# Servo_controller.net
KiCad netlist of a schematic drawn in Altium Designer
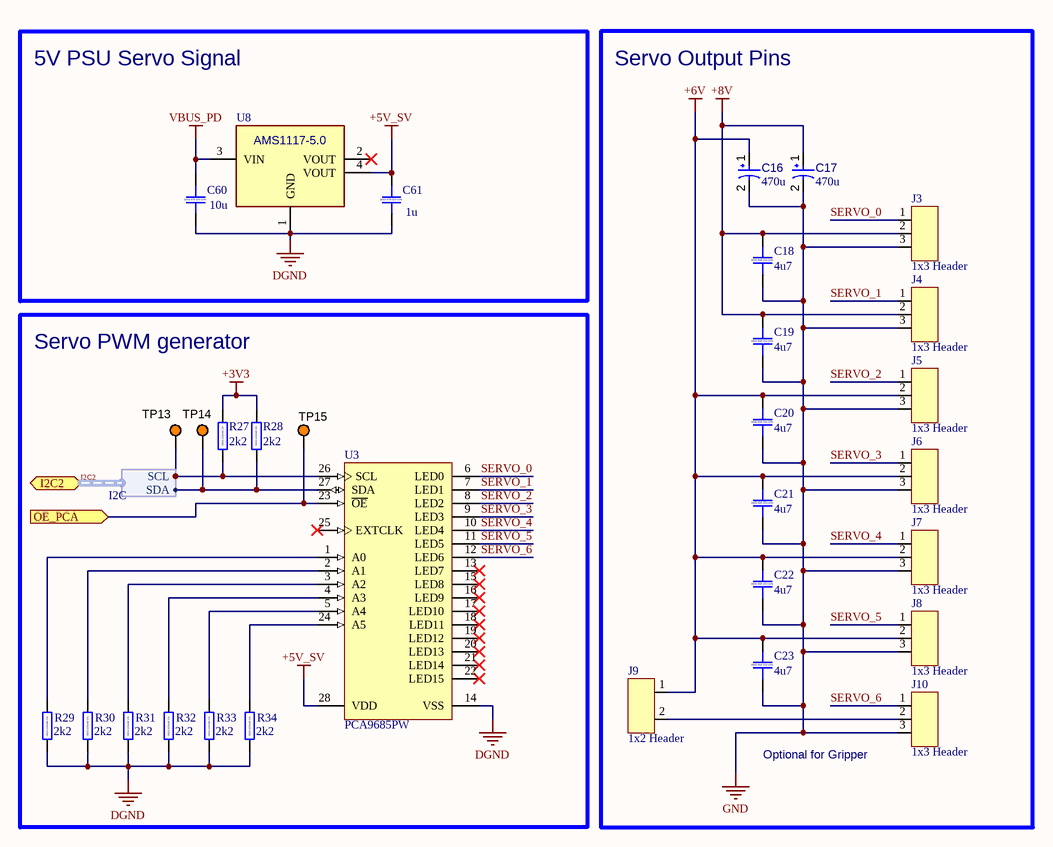
[diagram p0: Servo_controller.SchDoc]

(export (version "E")
  (design (tool "Eeschema 10.0.6"))
  (components
    (comp (ref "C16")
      (value "470u")
      (footprint "CAPPR65-500-2000X1000X2200")
      (description "Aluminum Electrolytic Capacitor, 2-Pin THD")
      (fields (field (name "MANUFACTURER") "Panasonic") (field (name "TOLERANCE") "20%"))
      (libsource (lib "Leonhard Waibl") (part "CAP-P-2"))
    )
    (comp (ref "C17")
      (value "470u")
      (footprint "CAPPR65-500-2000X1000X2200")
      (description "Aluminum Electrolytic Capacitor, 2-Pin THD")
      (fields (field (name "MANUFACTURER") "Panasonic") (field (name "TOLERANCE") "20%"))
      (libsource (lib "Leonhard Waibl") (part "CAP-P-2"))
    )
    (comp (ref "C18")
      (value "4u7")
      (footprint "CAP_0805")
      (description "Capacitor SMD 0805")
      (fields (field (name "SOURCE") "Schematic-Lib-PhilsLab.SchLib"))
      (libsource (lib "") (part "CAP_EL_NP_5MM_1"))
    )
    (comp (ref "C19")
      (value "4u7")
      (footprint "CAP_0805")
      (description "Capacitor SMD 0805")
      (fields (field (name "SOURCE") "Schematic-Lib-PhilsLab.SchLib"))
      (libsource (lib "") (part "CAP_EL_NP_5MM_1"))
    )
    (comp (ref "C20")
      (value "4u7")
      (footprint "CAP_0805")
      (description "Capacitor SMD 0805")
      (fields (field (name "SOURCE") "Schematic-Lib-PhilsLab.SchLib"))
      (libsource (lib "") (part "CAP_EL_NP_5MM_1"))
    )
    (comp (ref "C21")
      (value "4u7")
      (footprint "CAP_0805")
      (description "Capacitor SMD 0805")
      (fields (field (name "SOURCE") "Schematic-Lib-PhilsLab.SchLib"))
      (libsource (lib "") (part "CAP_EL_NP_5MM_1"))
    )
    (comp (ref "C22")
      (value "4u7")
      (footprint "CAP_0805")
      (description "Capacitor SMD 0805")
      (fields (field (name "SOURCE") "Schematic-Lib-PhilsLab.SchLib"))
      (libsource (lib "") (part "CAP_EL_NP_5MM_1"))
    )
    (comp (ref "C23")
      (value "4u7")
      (footprint "CAP_0805")
      (description "Capacitor SMD 0805")
      (fields (field (name "SOURCE") "Schematic-Lib-PhilsLab.SchLib"))
      (libsource (lib "") (part "CAP_EL_NP_5MM_1"))
    )
    (comp (ref "C60")
      (value "10u")
      (footprint "CAP_0603")
      (description "Capacitor SMD 0603")
      (fields (field (name "SOURCE") "Schematic-Lib-PhilsLab.SchLib"))
      (libsource (lib "Leonhard Waibl") (part "CAP_EL_NP_5MM"))
    )
    (comp (ref "C61")
      (value "1u")
      (footprint "CAP_0603")
      (description "Capacitor SMD 0603")
      (fields (field (name "SOURCE") "Schematic-Lib-PhilsLab.SchLib"))
      (libsource (lib "Leonhard Waibl") (part "CAP_EL_NP_5MM"))
    )
    (comp (ref "J3")
      (value "1x3 Header")
      (footprint "1x4 Header-Footprint-1")
      (libsource (lib "Leonhard Waibl") (part "1x3 Header"))
    )
    (comp (ref "J4")
      (value "1x3 Header")
      (footprint "1x4 Header-Footprint-1")
      (libsource (lib "Leonhard Waibl") (part "1x3 Header"))
    )
    (comp (ref "J5")
      (value "1x3 Header")
      (footprint "1x4 Header-Footprint-1")
      (libsource (lib "Leonhard Waibl") (part "1x3 Header"))
    )
    (comp (ref "J6")
      (value "1x3 Header")
      (footprint "1x4 Header-Footprint-1")
      (libsource (lib "Leonhard Waibl") (part "1x3 Header"))
    )
    (comp (ref "J7")
      (value "1x3 Header")
      (footprint "1x4 Header-Footprint-1")
      (libsource (lib "Leonhard Waibl") (part "1x3 Header"))
    )
    (comp (ref "J8")
      (value "1x3 Header")
      (footprint "1x4 Header-Footprint-1")
      (libsource (lib "Leonhard Waibl") (part "1x3 Header"))
    )
    (comp (ref "J9")
      (value "1x2 Header")
      (footprint "1x2 Header-Footprint-1")
      (libsource (lib "Leonhard Waibl") (part "1x2 Header-Symbol-1"))
    )
    (comp (ref "J10")
      (value "1x3 Header")
      (footprint "1x4 Header-Footprint-1")
      (libsource (lib "Leonhard Waibl") (part "1x3 Header"))
    )
    (comp (ref "R27")
      (value "2k2")
      (footprint "RES_0603")
      (description "Resistor 0603 100mW 1%")
      (fields (field (name "SOURCE") "Schematic-Lib-PhilsLab.SchLib"))
      (libsource (lib "Leonhard Waibl") (part "RES_5931"))
    )
    (comp (ref "R28")
      (value "2k2")
      (footprint "RES_0603")
      (description "Resistor 0603 100mW 1%")
      (fields (field (name "SOURCE") "Schematic-Lib-PhilsLab.SchLib"))
      (libsource (lib "Leonhard Waibl") (part "RES_5931"))
    )
    (comp (ref "R29")
      (value "2k2")
      (footprint "RES_0603")
      (description "Resistor 0603 100mW 1%")
      (fields (field (name "SOURCE") "Schematic-Lib-PhilsLab.SchLib"))
      (libsource (lib "Leonhard Waibl") (part "RES_5931"))
    )
    (comp (ref "R30")
      (value "2k2")
      (footprint "RES_0603")
      (description "Resistor 0603 100mW 1%")
      (fields (field (name "SOURCE") "Schematic-Lib-PhilsLab.SchLib"))
      (libsource (lib "Leonhard Waibl") (part "RES_5931"))
    )
    (comp (ref "R31")
      (value "2k2")
      (footprint "RES_0603")
      (description "Resistor 0603 100mW 1%")
      (fields (field (name "SOURCE") "Schematic-Lib-PhilsLab.SchLib"))
      (libsource (lib "Leonhard Waibl") (part "RES_5931"))
    )
    (comp (ref "R32")
      (value "2k2")
      (footprint "RES_0603")
      (description "Resistor 0603 100mW 1%")
      (fields (field (name "SOURCE") "Schematic-Lib-PhilsLab.SchLib"))
      (libsource (lib "Leonhard Waibl") (part "RES_5931"))
    )
    (comp (ref "R33")
      (value "2k2")
      (footprint "RES_0603")
      (description "Resistor 0603 100mW 1%")
      (fields (field (name "SOURCE") "Schematic-Lib-PhilsLab.SchLib"))
      (libsource (lib "Leonhard Waibl") (part "RES_5931"))
    )
    (comp (ref "R34")
      (value "2k2")
      (footprint "RES_0603")
      (description "Resistor 0603 100mW 1%")
      (fields (field (name "SOURCE") "Schematic-Lib-PhilsLab.SchLib"))
      (libsource (lib "Leonhard Waibl") (part "RES_5931"))
    )
    (comp (ref "TP13")
      (value "5003")
      (footprint "KSTN-5003")
      (description "Test Point, Orange, Height 4.6 mm, Tail Length 3 mm, 1-Pin THD, RoHS")
      (fields (field (name "MANUFACTURER") "Keystone"))
      (libsource (lib "Leonhard Waibl") (part "TESTPOINT_ORANGE"))
    )
    (comp (ref "TP14")
      (value "5003")
      (footprint "KSTN-5003")
      (description "Test Point, Orange, Height 4.6 mm, Tail Length 3 mm, 1-Pin THD, RoHS")
      (fields (field (name "MANUFACTURER") "Keystone"))
      (libsource (lib "Leonhard Waibl") (part "TESTPOINT_ORANGE"))
    )
    (comp (ref "TP15")
      (value "5003")
      (footprint "KSTN-5003")
      (description "Test Point, Orange, Height 4.6 mm, Tail Length 3 mm, 1-Pin THD, RoHS")
      (fields (field (name "MANUFACTURER") "Keystone"))
      (libsource (lib "Leonhard Waibl") (part "TESTPOINT_ORANGE"))
    )
    (comp (ref "U3")
      (value "PCA9685PW")
      (footprint "SOT361-1_V")
      (fields (field (name "PARTNUMBER") "PCA9685"))
      (libsource (lib "Altium Content Vault") (part "NXP-PCA9685-SOT361-1"))
    )
    (comp (ref "U8")
      (value "AMS1117-5.0")
      (footprint "FP-AMS1117-IPC_B")
      (description "Fixed Positive LDO Regulator, 5.0V, 1.3V Dropout, PDSO3")
      (libsource (lib "Leonhard Waibl") (part "8bdbb5f8e77002000e30dd2845d0354"))
    )
  )
  (nets
    (net (code "2") (name "+3V3") (class "Default")
      (node (ref "R27") (pin "2") (pinfunction "2_2") (pintype "passive"))
      (node (ref "R28") (pin "2") (pinfunction "2_2") (pintype "passive"))
    )
    (net (code "3") (name "+5V_SV") (class "Default")
      (node (ref "C61") (pin "1") (pinfunction "1_1") (pintype "passive"))
      (node (ref "U3") (pin "28") (pinfunction "VDD_28") (pintype "power_in"))
      (node (ref "U8") (pin "4") (pinfunction "VOUT_4") (pintype "passive"))
    )
    (net (code "4") (name "+6V") (class "Default")
      (node (ref "C16") (pin "1") (pinfunction "1_1") (pintype "passive"))
      (node (ref "C20") (pin "2") (pinfunction "2_2") (pintype "passive"))
      (node (ref "C21") (pin "2") (pinfunction "2_2") (pintype "passive"))
      (node (ref "C22") (pin "2") (pinfunction "2_2") (pintype "passive"))
      (node (ref "C23") (pin "2") (pinfunction "2_2") (pintype "passive"))
      (node (ref "J5") (pin "2") (pinfunction "2_2") (pintype "passive"))
      (node (ref "J6") (pin "2") (pinfunction "2_2") (pintype "passive"))
      (node (ref "J7") (pin "2") (pinfunction "2_2") (pintype "passive"))
      (node (ref "J8") (pin "2") (pinfunction "2_2") (pintype "passive"))
      (node (ref "J9") (pin "1") (pinfunction "1_1") (pintype "passive"))
    )
    (net (code "5") (name "+8V") (class "Default")
      (node (ref "C17") (pin "1") (pinfunction "1_1") (pintype "passive"))
      (node (ref "C18") (pin "2") (pinfunction "2_2") (pintype "passive"))
      (node (ref "C19") (pin "2") (pinfunction "2_2") (pintype "passive"))
      (node (ref "J3") (pin "2") (pinfunction "2_2") (pintype "passive"))
      (node (ref "J4") (pin "2") (pinfunction "2_2") (pintype "passive"))
    )
    (net (code "7") (name "/OE_PCA") (class "Default")
      (node (ref "TP15") (pin "1") (pinfunction "1_1") (pintype "passive"))
      (node (ref "U3") (pin "23") (pinfunction "~{OE}_23") (pintype "input"))
    )
    (net (code "8") (name "/SERVO_0") (class "Default")
      (node (ref "J3") (pin "1") (pinfunction "1_1") (pintype "passive"))
      (node (ref "U3") (pin "6") (pinfunction "LED0_6") (pintype "tri_state"))
    )
    (net (code "9") (name "/SERVO_1") (class "Default")
      (node (ref "J4") (pin "1") (pinfunction "1_1") (pintype "passive"))
      (node (ref "U3") (pin "7") (pinfunction "LED1_7") (pintype "tri_state"))
    )
    (net (code "10") (name "/SERVO_2") (class "Default")
      (node (ref "J5") (pin "1") (pinfunction "1_1") (pintype "passive"))
      (node (ref "U3") (pin "8") (pinfunction "LED2_8") (pintype "tri_state"))
    )
    (net (code "11") (name "/SERVO_3") (class "Default")
      (node (ref "J6") (pin "1") (pinfunction "1_1") (pintype "passive"))
      (node (ref "U3") (pin "9") (pinfunction "LED3_9") (pintype "tri_state"))
    )
    (net (code "12") (name "/SERVO_4") (class "Default")
      (node (ref "J7") (pin "1") (pinfunction "1_1") (pintype "passive"))
      (node (ref "U3") (pin "10") (pinfunction "LED4_10") (pintype "tri_state"))
    )
    (net (code "13") (name "/SERVO_5") (class "Default")
      (node (ref "J8") (pin "1") (pinfunction "1_1") (pintype "passive"))
      (node (ref "U3") (pin "11") (pinfunction "LED5_11") (pintype "tri_state"))
    )
    (net (code "14") (name "/SERVO_6") (class "Default")
      (node (ref "J10") (pin "1") (pinfunction "1_1") (pintype "passive"))
      (node (ref "U3") (pin "12") (pinfunction "LED6_12") (pintype "tri_state"))
    )
    (net (code "15") (name "DGND") (class "Default")
      (node (ref "C60") (pin "2") (pinfunction "2_2") (pintype "passive"))
      (node (ref "C61") (pin "2") (pinfunction "2_2") (pintype "passive"))
      (node (ref "R29") (pin "1") (pinfunction "1_1") (pintype "passive"))
      (node (ref "R30") (pin "1") (pinfunction "1_1") (pintype "passive"))
      (node (ref "R31") (pin "1") (pinfunction "1_1") (pintype "passive"))
      (node (ref "R32") (pin "1") (pinfunction "1_1") (pintype "passive"))
      (node (ref "R33") (pin "1") (pinfunction "1_1") (pintype "passive"))
      (node (ref "R34") (pin "1") (pinfunction "1_1") (pintype "passive"))
      (node (ref "U3") (pin "14") (pinfunction "VSS_14") (pintype "power_in"))
      (node (ref "U8") (pin "1") (pinfunction "GND_1") (pintype "power_in"))
    )
    (net (code "16") (name "GND") (class "Default")
      (node (ref "C16") (pin "2") (pinfunction "2_2") (pintype "passive"))
      (node (ref "C17") (pin "2") (pinfunction "2_2") (pintype "passive"))
      (node (ref "C18") (pin "1") (pinfunction "1_1") (pintype "passive"))
      (node (ref "C19") (pin "1") (pinfunction "1_1") (pintype "passive"))
      (node (ref "C20") (pin "1") (pinfunction "1_1") (pintype "passive"))
      (node (ref "C21") (pin "1") (pinfunction "1_1") (pintype "passive"))
      (node (ref "C22") (pin "1") (pinfunction "1_1") (pintype "passive"))
      (node (ref "C23") (pin "1") (pinfunction "1_1") (pintype "passive"))
      (node (ref "J10") (pin "3") (pinfunction "3_3") (pintype "passive"))
      (node (ref "J3") (pin "3") (pinfunction "3_3") (pintype "passive"))
      (node (ref "J4") (pin "3") (pinfunction "3_3") (pintype "passive"))
      (node (ref "J5") (pin "3") (pinfunction "3_3") (pintype "passive"))
      (node (ref "J6") (pin "3") (pinfunction "3_3") (pintype "passive"))
      (node (ref "J7") (pin "3") (pinfunction "3_3") (pintype "passive"))
      (node (ref "J8") (pin "3") (pinfunction "3_3") (pintype "passive"))
    )
    (net (code "17") (name "Net-(J10-Pad2)") (class "Default")
      (node (ref "J10") (pin "2") (pinfunction "2_2") (pintype "passive"))
      (node (ref "J9") (pin "2") (pinfunction "2_2") (pintype "passive"))
    )
    (net (code "18") (name "Net-(U3-A0)") (class "Default")
      (node (ref "R29") (pin "2") (pinfunction "2_2") (pintype "passive"))
      (node (ref "U3") (pin "1") (pinfunction "A0_1") (pintype "input"))
    )
    (net (code "19") (name "Net-(U3-A1)") (class "Default")
      (node (ref "R30") (pin "2") (pinfunction "2_2") (pintype "passive"))
      (node (ref "U3") (pin "2") (pinfunction "A1_2") (pintype "input"))
    )
    (net (code "20") (name "Net-(U3-A2)") (class "Default")
      (node (ref "R31") (pin "2") (pinfunction "2_2") (pintype "passive"))
      (node (ref "U3") (pin "3") (pinfunction "A2_3") (pintype "input"))
    )
    (net (code "21") (name "Net-(U3-A3)") (class "Default")
      (node (ref "R32") (pin "2") (pinfunction "2_2") (pintype "passive"))
      (node (ref "U3") (pin "4") (pinfunction "A3_4") (pintype "input"))
    )
    (net (code "22") (name "Net-(U3-A4)") (class "Default")
      (node (ref "R33") (pin "2") (pinfunction "2_2") (pintype "passive"))
      (node (ref "U3") (pin "5") (pinfunction "A4_5") (pintype "input"))
    )
    (net (code "23") (name "Net-(U3-A5)") (class "Default")
      (node (ref "R34") (pin "2") (pinfunction "2_2") (pintype "passive"))
      (node (ref "U3") (pin "24") (pinfunction "A5_24") (pintype "input"))
    )
    (net (code "24") (name "Net-(U3-SCL)") (class "Default")
      (node (ref "R27") (pin "1") (pinfunction "1_1") (pintype "passive"))
      (node (ref "TP13") (pin "1") (pinfunction "1_1") (pintype "passive"))
      (node (ref "U3") (pin "26") (pinfunction "SCL_26") (pintype "input"))
    )
    (net (code "25") (name "Net-(U3-SDA)") (class "Default")
      (node (ref "R28") (pin "1") (pinfunction "1_1") (pintype "passive"))
      (node (ref "TP14") (pin "1") (pinfunction "1_1") (pintype "passive"))
      (node (ref "U3") (pin "27") (pinfunction "SDA_27") (pintype "bidirectional"))
    )
    (net (code "26") (name "VBUS_PD") (class "Default")
      (node (ref "C60") (pin "1") (pinfunction "1_1") (pintype "passive"))
      (node (ref "U8") (pin "3") (pinfunction "VIN_3") (pintype "power_in"))
    )
    (net (code "27") (name "unconnected-(U3-EXTCLK-Pad25)") (class "Default")
      (node (ref "U3") (pin "25") (pinfunction "EXTCLK_25") (pintype "input+no_connect"))
    )
    (net (code "28") (name "unconnected-(U3-LED7-Pad13)") (class "Default")
      (node (ref "U3") (pin "13") (pinfunction "LED7_13") (pintype "tri_state+no_connect"))
    )
    (net (code "29") (name "unconnected-(U3-LED8-Pad15)") (class "Default")
      (node (ref "U3") (pin "15") (pinfunction "LED8_15") (pintype "tri_state+no_connect"))
    )
    (net (code "30") (name "unconnected-(U3-LED9-Pad16)") (class "Default")
      (node (ref "U3") (pin "16") (pinfunction "LED9_16") (pintype "tri_state+no_connect"))
    )
    (net (code "31") (name "unconnected-(U3-LED10-Pad17)") (class "Default")
      (node (ref "U3") (pin "17") (pinfunction "LED10_17") (pintype "tri_state+no_connect"))
    )
    (net (code "32") (name "unconnected-(U3-LED11-Pad18)") (class "Default")
      (node (ref "U3") (pin "18") (pinfunction "LED11_18") (pintype "tri_state+no_connect"))
    )
    (net (code "33") (name "unconnected-(U3-LED12-Pad19)") (class "Default")
      (node (ref "U3") (pin "19") (pinfunction "LED12_19") (pintype "tri_state+no_connect"))
    )
    (net (code "34") (name "unconnected-(U3-LED13-Pad20)") (class "Default")
      (node (ref "U3") (pin "20") (pinfunction "LED13_20") (pintype "tri_state+no_connect"))
    )
    (net (code "35") (name "unconnected-(U3-LED14-Pad21)") (class "Default")
      (node (ref "U3") (pin "21") (pinfunction "LED14_21") (pintype "tri_state+no_connect"))
    )
    (net (code "36") (name "unconnected-(U3-LED15-Pad22)") (class "Default")
      (node (ref "U3") (pin "22") (pinfunction "LED15_22") (pintype "tri_state+no_connect"))
    )
    (net (code "37") (name "unconnected-(U8-VOUT-Pad2)") (class "Default")
      (node (ref "U8") (pin "2") (pinfunction "VOUT_2") (pintype "passive+no_connect"))
    )
  )
)
